# Peripheral.net
KiCad netlist of a schematic drawn in Altium Designer
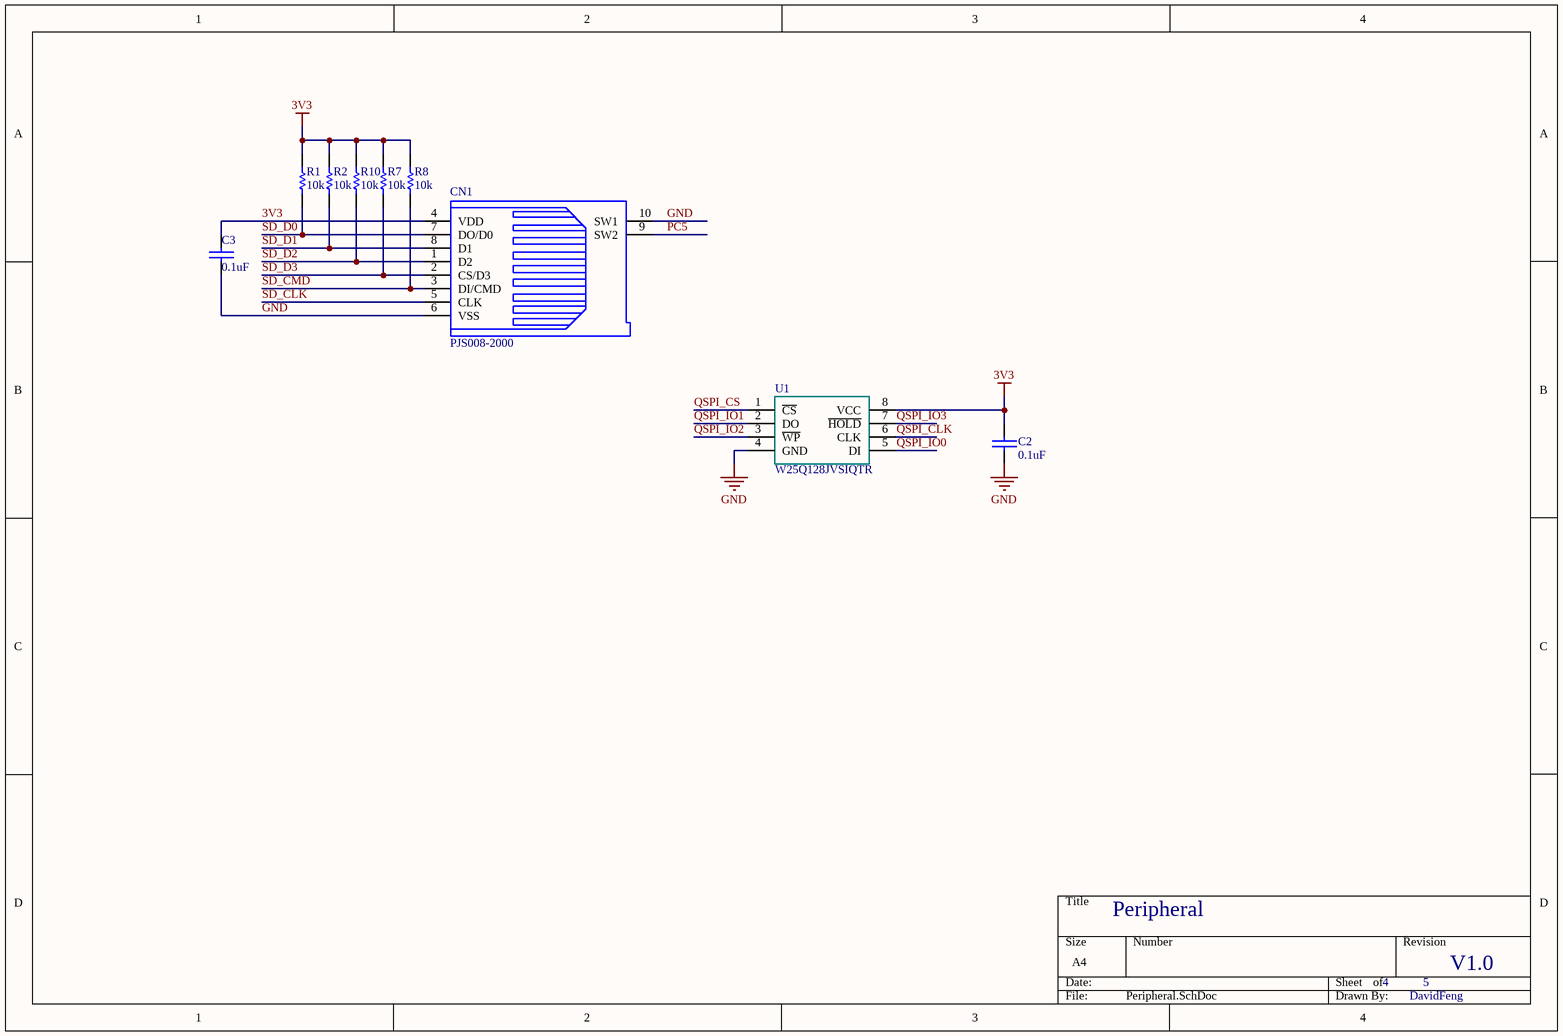
[diagram p0: Peripheral.SchDoc]

(export (version "E")
  (design (tool "Eeschema 10.0.6"))
  (components
    (comp (ref "C2")
      (value "0.1uF")
      (footprint "c0603")
      (description "Capacitor")
      (libsource (lib "Genius_Schlib") (part "CAP"))
    )
    (comp (ref "C3")
      (value "0.1uF")
      (footprint "c0603")
      (description "Capacitor")
      (libsource (lib "Genius_Schlib") (part "CAP"))
    )
    (comp (ref "CN1")
      (value "PJS008-2000")
      (footprint "TF_CARD")
      (libsource (lib "Genius_Schlib") (part "TF_CARD"))
    )
    (comp (ref "R1")
      (value "10k")
      (footprint "R0603")
      (description "Resistor")
      (fields (field (name "PUBLISHER") "Altium Limited"))
      (libsource (lib "Miscellaneous Devices") (part "Res1"))
    )
    (comp (ref "R2")
      (value "10k")
      (footprint "R0603")
      (description "Resistor")
      (fields (field (name "PUBLISHER") "Altium Limited"))
      (libsource (lib "Miscellaneous Devices") (part "Res1"))
    )
    (comp (ref "R7")
      (value "10k")
      (footprint "R0603")
      (description "Resistor")
      (fields (field (name "PUBLISHER") "Altium Limited"))
      (libsource (lib "Miscellaneous Devices") (part "Res1"))
    )
    (comp (ref "R8")
      (value "10k")
      (footprint "R0603")
      (description "Resistor")
      (fields (field (name "PUBLISHER") "Altium Limited"))
      (libsource (lib "Miscellaneous Devices") (part "Res1"))
    )
    (comp (ref "R10")
      (value "10k")
      (footprint "R0603")
      (description "Resistor")
      (fields (field (name "PUBLISHER") "Altium Limited"))
      (libsource (lib "Miscellaneous Devices") (part "Res1"))
    )
    (comp (ref "U1")
      (value "W25Q128JVSIQTR")
      (footprint "SOIC127P800-8N")
      (description "64M-BIT  SERIAL FLASH MEMORY")
      (libsource (lib "Genius_Schlib") (part "W25QXX"))
    )
  )
  (nets
    (net (code "1") (name "/PC5") (class "Default")
      (node (ref "CN1") (pin "9") (pinfunction "SW2_9") (pintype "passive"))
    )
    (net (code "2") (name "/QSPI_CLK") (class "Default")
      (node (ref "U1") (pin "6") (pinfunction "CLK_6") (pintype "passive"))
    )
    (net (code "3") (name "/QSPI_CS") (class "Default")
      (node (ref "U1") (pin "1") (pinfunction "~{CS}_1") (pintype "passive"))
    )
    (net (code "4") (name "/QSPI_IO0") (class "Default")
      (node (ref "U1") (pin "5") (pinfunction "DI_5") (pintype "passive"))
    )
    (net (code "5") (name "/QSPI_IO1") (class "Default")
      (node (ref "U1") (pin "2") (pinfunction "DO_2") (pintype "passive"))
    )
    (net (code "6") (name "/QSPI_IO2") (class "Default")
      (node (ref "U1") (pin "3") (pinfunction "~{WP}_3") (pintype "passive"))
    )
    (net (code "7") (name "/QSPI_IO3") (class "Default")
      (node (ref "U1") (pin "7") (pinfunction "~{HOLD}_7") (pintype "passive"))
    )
    (net (code "8") (name "/SD_CLK") (class "Default")
      (node (ref "CN1") (pin "5") (pinfunction "CLK_5") (pintype "passive"))
    )
    (net (code "9") (name "/SD_CMD") (class "Default")
      (node (ref "CN1") (pin "3") (pinfunction "DI/CMD_3") (pintype "passive"))
      (node (ref "R8") (pin "2") (pinfunction "2_2") (pintype "passive"))
    )
    (net (code "10") (name "/SD_D0") (class "Default")
      (node (ref "CN1") (pin "7") (pinfunction "DO/D0_7") (pintype "passive"))
      (node (ref "R1") (pin "2") (pinfunction "2_2") (pintype "passive"))
    )
    (net (code "11") (name "/SD_D1") (class "Default")
      (node (ref "CN1") (pin "8") (pinfunction "D1_8") (pintype "passive"))
      (node (ref "R2") (pin "2") (pinfunction "2_2") (pintype "passive"))
    )
    (net (code "12") (name "/SD_D2") (class "Default")
      (node (ref "CN1") (pin "1") (pinfunction "D2_1") (pintype "passive"))
      (node (ref "R10") (pin "2") (pinfunction "2_2") (pintype "passive"))
    )
    (net (code "13") (name "/SD_D3") (class "Default")
      (node (ref "CN1") (pin "2") (pinfunction "CS/D3_2") (pintype "passive"))
      (node (ref "R7") (pin "2") (pinfunction "2_2") (pintype "passive"))
    )
    (net (code "14") (name "3V3") (class "Default")
      (node (ref "C2") (pin "1") (pinfunction "1_1") (pintype "passive"))
      (node (ref "C3") (pin "1") (pinfunction "1_1") (pintype "passive"))
      (node (ref "CN1") (pin "4") (pinfunction "VDD_4") (pintype "passive"))
      (node (ref "R1") (pin "1") (pinfunction "1_1") (pintype "passive"))
      (node (ref "R10") (pin "1") (pinfunction "1_1") (pintype "passive"))
      (node (ref "R2") (pin "1") (pinfunction "1_1") (pintype "passive"))
      (node (ref "R7") (pin "1") (pinfunction "1_1") (pintype "passive"))
      (node (ref "R8") (pin "1") (pinfunction "1_1") (pintype "passive"))
      (node (ref "U1") (pin "8") (pinfunction "VCC_8") (pintype "passive"))
    )
    (net (code "15") (name "GND") (class "Default")
      (node (ref "C2") (pin "2") (pinfunction "2_2") (pintype "passive"))
      (node (ref "C3") (pin "2") (pinfunction "2_2") (pintype "passive"))
      (node (ref "CN1") (pin "10") (pinfunction "SW1_10") (pintype "passive"))
      (node (ref "CN1") (pin "6") (pinfunction "VSS_6") (pintype "passive"))
      (node (ref "U1") (pin "4") (pinfunction "GND_4") (pintype "passive"))
    )
  )
)
